# design.net
KiCad netlist of a schematic drawn in Altium Designer
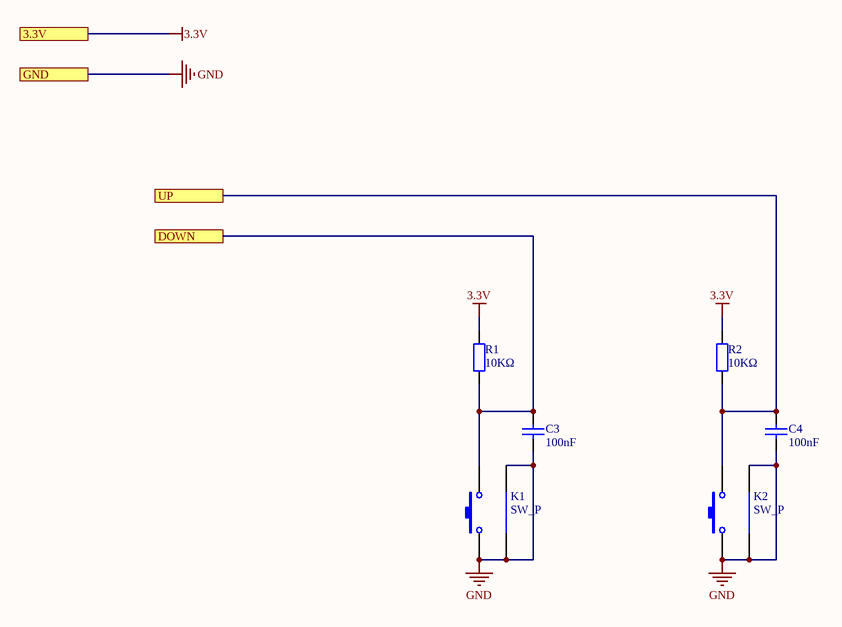
[diagram p0: 按键模块.SchDoc]

(export (version "E")
  (design (tool "Eeschema 10.0.6"))
  (components
    (comp (ref "C3")
      (value "100nF")
      (footprint "LC-0603_C")
      (description "贴片电容")
      (libsource (lib "Miscellaneous Devices LC") (part "0603 100nF (104) 10% 50V"))
    )
    (comp (ref "C4")
      (value "100nF")
      (footprint "LC-0603_C")
      (description "贴片电容")
      (libsource (lib "Miscellaneous Devices LC") (part "0603 100nF (104) 10% 50V"))
    )
    (comp (ref "K1")
      (value "SW_P")
      (footprint "KEY-TH_K2-1112SA-AXXW-XX")
      (description "轻触开关侧")
      (libsource (lib "user_Library") (part "SW_P"))
    )
    (comp (ref "K2")
      (value "SW_P")
      (footprint "KEY-TH_K2-1112SA-AXXW-XX")
      (description "轻触开关侧")
      (libsource (lib "user_Library") (part "SW_P"))
    )
    (comp (ref "R1")
      (value "10KΩ")
      (footprint "LC-0603_R")
      (description "贴片电阻")
      (libsource (lib "Miscellaneous Devices LC") (part "0603 10KΩ (1002) 1%"))
    )
    (comp (ref "R2")
      (value "10KΩ")
      (footprint "LC-0603_R")
      (description "贴片电阻")
      (libsource (lib "Miscellaneous Devices LC") (part "0603 10KΩ (1002) 1%"))
    )
  )
  (nets
    (net (code "1") (name "/DOWN") (class "Default")
      (node (ref "C3") (pin "2") (pinfunction "2_2") (pintype "passive"))
      (node (ref "K1") (pin "2") (pinfunction "2_2") (pintype "passive"))
      (node (ref "R1") (pin "1") (pinfunction "1_1") (pintype "passive"))
    )
    (net (code "2") (name "/UP") (class "Default")
      (node (ref "C4") (pin "2") (pinfunction "2_2") (pintype "passive"))
      (node (ref "K2") (pin "2") (pinfunction "2_2") (pintype "passive"))
      (node (ref "R2") (pin "1") (pinfunction "1_1") (pintype "passive"))
    )
    (net (code "3") (name "3.3V") (class "Default")
      (node (ref "R1") (pin "2") (pinfunction "2_2") (pintype "passive"))
      (node (ref "R2") (pin "2") (pinfunction "2_2") (pintype "passive"))
    )
    (net (code "4") (name "GND") (class "Default")
      (node (ref "C3") (pin "1") (pinfunction "1_1") (pintype "passive"))
      (node (ref "C4") (pin "1") (pinfunction "1_1") (pintype "passive"))
      (node (ref "K1") (pin "1") (pinfunction "1_1") (pintype "passive"))
      (node (ref "K1") (pin "3") (pinfunction "3_3") (pintype "passive"))
      (node (ref "K1") (pin "4") (pinfunction "4_4") (pintype "passive"))
      (node (ref "K2") (pin "1") (pinfunction "1_1") (pintype "passive"))
      (node (ref "K2") (pin "3") (pinfunction "3_3") (pintype "passive"))
      (node (ref "K2") (pin "4") (pinfunction "4_4") (pintype "passive"))
    )
  )
)
